# Sheet1.net
KiCad netlist of a schematic drawn in Altium Designer
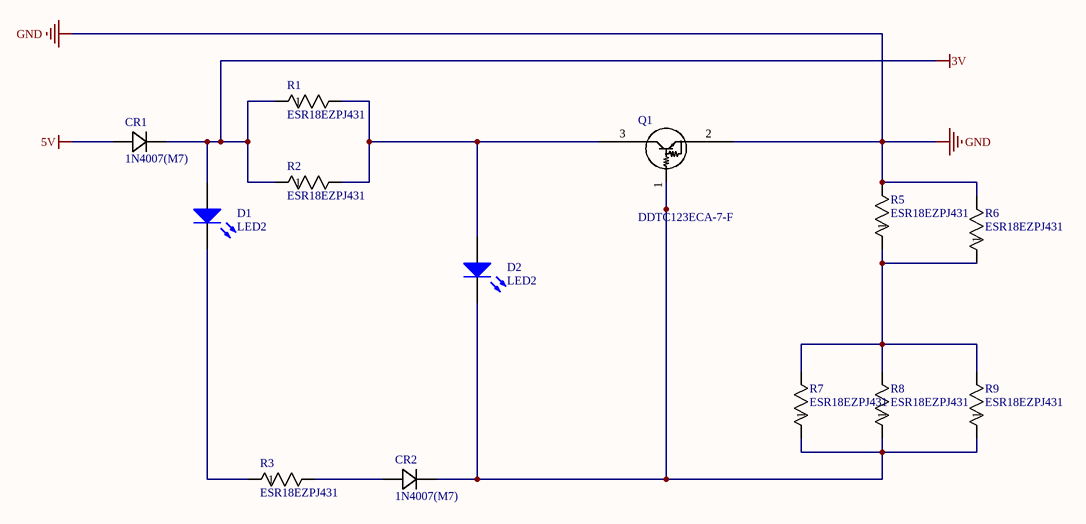
[diagram p0: Sheet1.SchDoc]

(export (version "E")
  (design (tool "Eeschema 10.0.6"))
  (components
    (comp (ref "CR1")
      (value "1N4007(M7)")
      (footprint "CR_1N4007(M7)_YTS")
      (description "No Description Available")
      (fields (field (name "COPYRIGHT") "Copyright (C) 2022 Ultra Librarian. All rights reserved."))
      (libsource (lib "1N4007_M7_") (part "1N4007(M7)"))
    )
    (comp (ref "CR2")
      (value "1N4007(M7)")
      (footprint "CR_1N4007(M7)_YTS")
      (description "No Description Available")
      (fields (field (name "COPYRIGHT") "Copyright (C) 2022 Ultra Librarian. All rights reserved."))
      (libsource (lib "1N4007_M7_") (part "1N4007(M7)"))
    )
    (comp (ref "D1")
      (value "LED2")
      (footprint "3.2X1.6X1.1")
      (description "Typical RED, GREEN, YELLOW, AMBER GaAs LED")
      (fields (field (name "PUBLISHER") "Altium Limited"))
      (libsource (lib "Miscellaneous Devices") (part "LED2"))
    )
    (comp (ref "D2")
      (value "LED2")
      (footprint "3.2X1.6X1.1")
      (description "Typical RED, GREEN, YELLOW, AMBER GaAs LED")
      (fields (field (name "PUBLISHER") "Altium Limited"))
      (libsource (lib "Miscellaneous Devices") (part "LED2"))
    )
    (comp (ref "Q1")
      (value "DDTC123ECA-7-F")
      (footprint "SOT23_DIO")
      (description "No Description Available")
      (fields (field (name "COPYRIGHT") "Copyright (C) 2022 Ultra Librarian. All rights reserved."))
      (libsource (lib "DDTC123ECA-7-F") (part "DDTC123ECA-7-F"))
    )
    (comp (ref "R1")
      (value "ESR18EZPJ431")
      (footprint "RES_R1206_ROM")
      (description "No Description Available")
      (fields (field (name "COPYRIGHT") "Copyright (C) 2022 Ultra Librarian. All rights reserved."))
      (libsource (lib "ESR18EZPJ431") (part "ESR18EZPJ431"))
    )
    (comp (ref "R2")
      (value "ESR18EZPJ431")
      (footprint "RES_R1206_ROM")
      (description "No Description Available")
      (fields (field (name "COPYRIGHT") "Copyright (C) 2022 Ultra Librarian. All rights reserved."))
      (libsource (lib "ESR18EZPJ431") (part "ESR18EZPJ431"))
    )
    (comp (ref "R3")
      (value "ESR18EZPJ431")
      (footprint "RES_R1206_ROM")
      (description "No Description Available")
      (fields (field (name "COPYRIGHT") "Copyright (C) 2022 Ultra Librarian. All rights reserved."))
      (libsource (lib "ESR18EZPJ431") (part "ESR18EZPJ431"))
    )
    (comp (ref "R5")
      (value "ESR18EZPJ431")
      (footprint "RES_R1206_ROM")
      (description "No Description Available")
      (fields (field (name "COPYRIGHT") "Copyright (C) 2022 Ultra Librarian. All rights reserved."))
      (libsource (lib "ESR18EZPJ431") (part "ESR18EZPJ431"))
    )
    (comp (ref "R6")
      (value "ESR18EZPJ431")
      (footprint "RES_R1206_ROM")
      (description "No Description Available")
      (fields (field (name "COPYRIGHT") "Copyright (C) 2022 Ultra Librarian. All rights reserved."))
      (libsource (lib "ESR18EZPJ431") (part "ESR18EZPJ431"))
    )
    (comp (ref "R7")
      (value "ESR18EZPJ431")
      (footprint "RES_R1206_ROM")
      (description "No Description Available")
      (fields (field (name "COPYRIGHT") "Copyright (C) 2022 Ultra Librarian. All rights reserved."))
      (libsource (lib "ESR18EZPJ431") (part "ESR18EZPJ431"))
    )
    (comp (ref "R8")
      (value "ESR18EZPJ431")
      (footprint "RES_R1206_ROM")
      (description "No Description Available")
      (fields (field (name "COPYRIGHT") "Copyright (C) 2022 Ultra Librarian. All rights reserved."))
      (libsource (lib "ESR18EZPJ431") (part "ESR18EZPJ431"))
    )
    (comp (ref "R9")
      (value "ESR18EZPJ431")
      (footprint "RES_R1206_ROM")
      (description "No Description Available")
      (fields (field (name "COPYRIGHT") "Copyright (C) 2022 Ultra Librarian. All rights reserved."))
      (libsource (lib "ESR18EZPJ431") (part "ESR18EZPJ431"))
    )
  )
  (nets
    (net (code "1") (name "3V") (class "Default")
      (node (ref "CR1") (pin "1") (pinfunction "1_1") (pintype "passive"))
      (node (ref "D1") (pin "1") (pinfunction "A_1") (pintype "passive"))
      (node (ref "R1") (pin "1") (pinfunction "1_1") (pintype "passive"))
      (node (ref "R2") (pin "1") (pinfunction "1_1") (pintype "passive"))
    )
    (net (code "2") (name "5V") (class "Default")
      (node (ref "CR1") (pin "2") (pinfunction "2_2") (pintype "passive"))
    )
    (net (code "3") (name "GND") (class "Default")
      (node (ref "Q1") (pin "2") (pinfunction "2_2") (pintype "passive"))
      (node (ref "R5") (pin "2") (pinfunction "2_2") (pintype "passive"))
      (node (ref "R6") (pin "2") (pinfunction "2_2") (pintype "passive"))
    )
    (net (code "4") (name "Net-(CR2-Pad2)") (class "Default")
      (node (ref "CR2") (pin "2") (pinfunction "2_2") (pintype "passive"))
      (node (ref "R3") (pin "2") (pinfunction "2_2") (pintype "passive"))
    )
    (net (code "5") (name "Net-(D1-K)") (class "Default")
      (node (ref "D1") (pin "2") (pinfunction "K_2") (pintype "passive"))
      (node (ref "R3") (pin "1") (pinfunction "1_1") (pintype "passive"))
    )
    (net (code "6") (name "Net-(D2-A)") (class "Default")
      (node (ref "D2") (pin "1") (pinfunction "A_1") (pintype "passive"))
      (node (ref "Q1") (pin "3") (pinfunction "3_3") (pintype "passive"))
      (node (ref "R1") (pin "2") (pinfunction "2_2") (pintype "passive"))
      (node (ref "R2") (pin "2") (pinfunction "2_2") (pintype "passive"))
    )
    (net (code "7") (name "Net-(D2-K)") (class "Default")
      (node (ref "CR2") (pin "1") (pinfunction "1_1") (pintype "passive"))
      (node (ref "D2") (pin "2") (pinfunction "K_2") (pintype "passive"))
      (node (ref "Q1") (pin "1") (pinfunction "1_1") (pintype "passive"))
      (node (ref "R7") (pin "1") (pinfunction "1_1") (pintype "passive"))
      (node (ref "R8") (pin "1") (pinfunction "1_1") (pintype "passive"))
      (node (ref "R9") (pin "1") (pinfunction "1_1") (pintype "passive"))
    )
    (net (code "8") (name "Net-(R5-Pad1)") (class "Default")
      (node (ref "R5") (pin "1") (pinfunction "1_1") (pintype "passive"))
      (node (ref "R6") (pin "1") (pinfunction "1_1") (pintype "passive"))
      (node (ref "R7") (pin "2") (pinfunction "2_2") (pintype "passive"))
      (node (ref "R8") (pin "2") (pinfunction "2_2") (pintype "passive"))
      (node (ref "R9") (pin "2") (pinfunction "2_2") (pintype "passive"))
    )
  )
)
